# tie-flash-cfg.net
KiCad netlist of a schematic drawn in Altium Designer
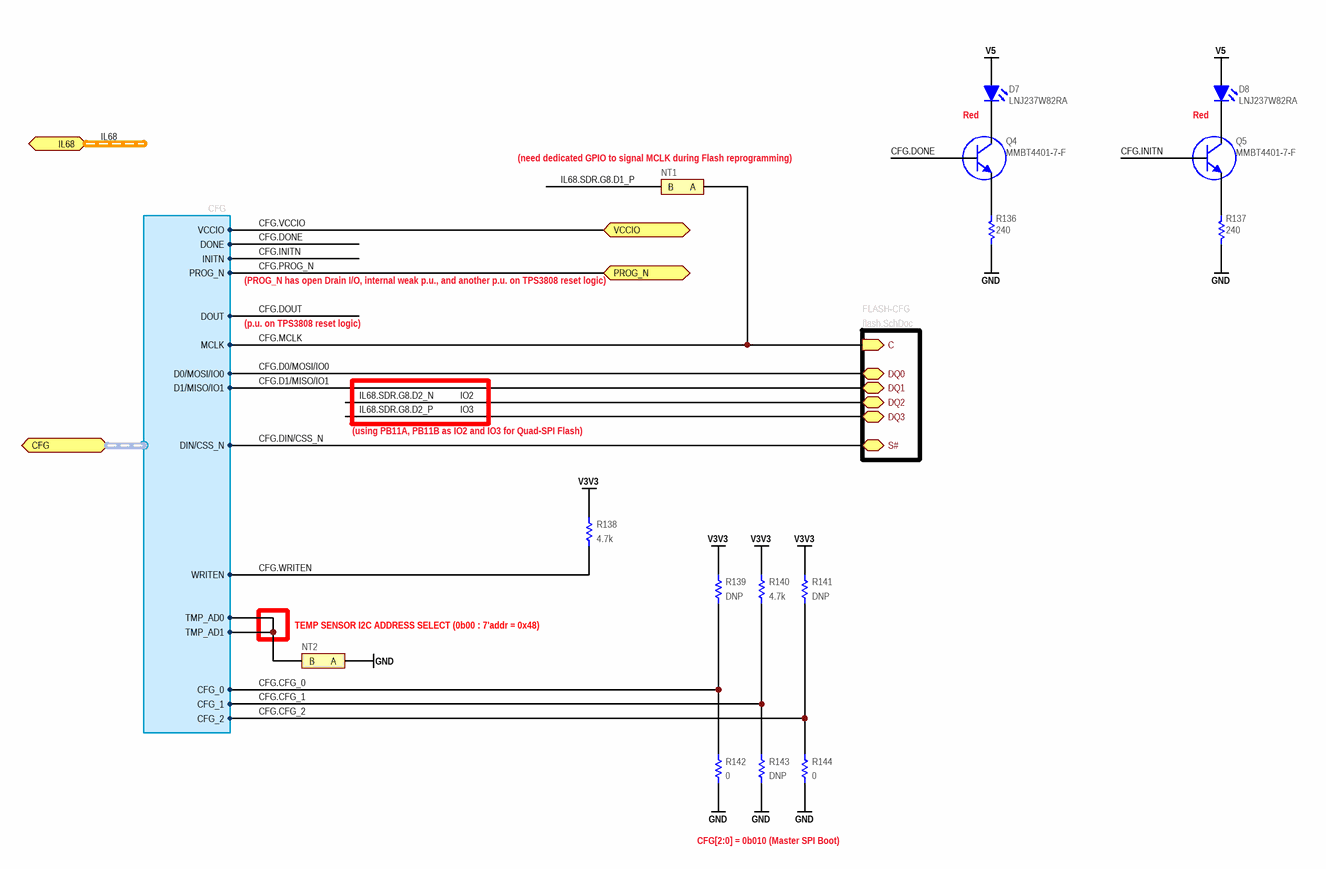
[diagram p0: tie-flash-cfg.SchDoc]

(export (version "E")
  (design (tool "Eeschema 10.0.6"))
  (components
    (comp (ref "D7")
      (value "LNJ237W82RA")
      (footprint "0603_LED")
      (description "LED, SMT 0603, Color Red, 5mA, 1.85V")
      (fields (field (name "MANUFACTURER") "Panasonic"))
      (libsource (lib "generic") (part "LED0603RD"))
    )
    (comp (ref "D8")
      (value "LNJ237W82RA")
      (footprint "0603_LED")
      (description "LED, SMT 0603, Color Red, 5mA, 1.85V")
      (fields (field (name "MANUFACTURER") "Panasonic"))
      (libsource (lib "generic") (part "LED0603RD"))
    )
    (comp (ref "NT1")
      (value "NET_TIE")
      (footprint "NET_TIE")
      (libsource (lib "copper_suicide") (part "NET_TIE"))
    )
    (comp (ref "NT2")
      (value "NET_TIE")
      (footprint "NET_TIE")
      (libsource (lib "copper_suicide") (part "NET_TIE"))
    )
    (comp (ref "Q4")
      (value "MMBT4401-7-F")
      (footprint "generic:SOT23")
      (description "NPN Small Signal Transistor SMD SOT-23")
      (fields (field (name "MANUFACTURER P/N") "MMBT4401-7-F") (field (name "MANUFACTURER") "Diodes, Inc."))
      (libsource (lib "diodes_inc") (part "MMBT4401-7-F"))
    )
    (comp (ref "Q5")
      (value "MMBT4401-7-F")
      (footprint "generic:SOT23")
      (description "NPN Small Signal Transistor SMD SOT-23")
      (fields (field (name "MANUFACTURER P/N") "MMBT4401-7-F") (field (name "MANUFACTURER") "Diodes, Inc."))
      (libsource (lib "diodes_inc") (part "MMBT4401-7-F"))
    )
    (comp (ref "R136")
      (value "240")
      (footprint "RESC1005X40N")
      (description "Thick Film Resistor 240 ±1% 0.1W 75V 0402")
      (fields (field (name "TOLERANCE") "±1%") (field (name "MANUFACTURER") "Panasonic"))
      (libsource (lib "generic") (part "RES"))
    )
    (comp (ref "R137")
      (value "240")
      (footprint "RESC1005X40N")
      (description "Thick Film Resistor 240 ±1% 0.1W 75V 0402")
      (fields (field (name "TOLERANCE") "±1%") (field (name "MANUFACTURER") "Panasonic"))
      (libsource (lib "generic") (part "RES"))
    )
    (comp (ref "R138")
      (value "4.7k")
      (footprint "RESC1005X40N")
      (description "Thick Film Resistor 4.7k ±1% 0.1W 75V 0402")
      (fields (field (name "TOLERANCE") "±1%") (field (name "MANUFACTURER") "Panasonic"))
      (libsource (lib "generic") (part "RES"))
    )
    (comp (ref "R139")
      (value "ERJ-3EKF4701V")
      (footprint "RESC1608X55N")
      (description "Thick Film Resistor 4.7k ±1% 0.1W 50V 0603")
      (fields
        (field (name "TOLERANCE") "±1%")
        (field (name "MANUFACTURER") "Panasonic")
        (field (name "DO NOT PLACE") "DNP")
      )
      (libsource (lib "generic") (part "RES"))
    )
    (comp (ref "R140")
      (value "4.7k")
      (footprint "RESC1608X55N")
      (description "Thick Film Resistor 4.7k ±1% 0.1W 50V 0603")
      (fields (field (name "TOLERANCE") "±1%") (field (name "MANUFACTURER") "Panasonic"))
      (libsource (lib "generic") (part "RES"))
    )
    (comp (ref "R141")
      (value "ERJ-3EKF4701V")
      (footprint "RESC1608X55N")
      (description "Thick Film Resistor 4.7k ±1% 0.1W 50V 0603")
      (fields
        (field (name "TOLERANCE") "±1%")
        (field (name "MANUFACTURER") "Panasonic")
        (field (name "DO NOT PLACE") "DNP")
      )
      (libsource (lib "generic") (part "RES"))
    )
    (comp (ref "R142")
      (value "0")
      (footprint "RESC1608X55N")
      (description "Thick Film Resistor Jumper 0 1A 0603")
      (fields (field (name "TOLERANCE") "±1%") (field (name "MANUFACTURER") "Panasonic"))
      (libsource (lib "generic") (part "RES"))
    )
    (comp (ref "R143")
      (value "ERJ-3GEY0R00V")
      (footprint "RESC1608X55N")
      (description "Thick Film Resistor Jumper 0 1A 0603")
      (fields
        (field (name "TOLERANCE") "±1%")
        (field (name "MANUFACTURER") "Panasonic")
        (field (name "DO NOT PLACE") "DNP")
      )
      (libsource (lib "generic") (part "RES"))
    )
    (comp (ref "R144")
      (value "0")
      (footprint "RESC1608X55N")
      (description "Thick Film Resistor Jumper 0 1A 0603")
      (fields (field (name "TOLERANCE") "±1%") (field (name "MANUFACTURER") "Panasonic"))
      (libsource (lib "generic") (part "RES"))
    )
  )
  (nets
    (net (code "3") (name "/CFG.CFG_0") (class "Default")
      (node (ref "R139") (pin "1") (pinfunction "1_1") (pintype "passive"))
      (node (ref "R142") (pin "2") (pinfunction "2_2") (pintype "passive"))
    )
    (net (code "4") (name "/CFG.CFG_1") (class "Default")
      (node (ref "R140") (pin "1") (pinfunction "1_1") (pintype "passive"))
      (node (ref "R143") (pin "2") (pinfunction "2_2") (pintype "passive"))
    )
    (net (code "5") (name "/CFG.CFG_2") (class "Default")
      (node (ref "R141") (pin "1") (pinfunction "1_1") (pintype "passive"))
      (node (ref "R144") (pin "2") (pinfunction "2_2") (pintype "passive"))
    )
    (net (code "9") (name "/CFG.DONE") (class "Default")
      (node (ref "Q4") (pin "1") (pinfunction "B_1") (pintype "passive"))
    )
    (net (code "11") (name "/CFG.INITN") (class "Default")
      (node (ref "Q5") (pin "1") (pinfunction "B_1") (pintype "passive"))
    )
    (net (code "12") (name "/CFG.MCLK") (class "Default")
      (node (ref "NT1") (pin "A") (pinfunction "A_A") (pintype "passive"))
    )
    (net (code "15") (name "/CFG.WRITEN") (class "Default")
      (node (ref "R138") (pin "1") (pinfunction "1_1") (pintype "passive"))
    )
    (net (code "16") (name "/IL68.SDR.G8.D1_P") (class "Default")
      (node (ref "NT1") (pin "B") (pinfunction "B_B") (pintype "passive"))
    )
    (net (code "19") (name "/TMP_AD0") (class "Default")
      (node (ref "NT2") (pin "B") (pinfunction "B_B") (pintype "passive"))
    )
    (net (code "22") (name "GND") (class "Default")
      (node (ref "NT2") (pin "A") (pinfunction "A_A") (pintype "passive"))
      (node (ref "R136") (pin "2") (pinfunction "2_2") (pintype "passive"))
      (node (ref "R137") (pin "2") (pinfunction "2_2") (pintype "passive"))
      (node (ref "R142") (pin "1") (pinfunction "1_1") (pintype "passive"))
      (node (ref "R143") (pin "1") (pinfunction "1_1") (pintype "passive"))
      (node (ref "R144") (pin "1") (pinfunction "1_1") (pintype "passive"))
    )
    (net (code "23") (name "Net-(D7-K)") (class "Default")
      (node (ref "D7") (pin "2") (pinfunction "K_2") (pintype "passive"))
      (node (ref "Q4") (pin "3") (pinfunction "C_3") (pintype "passive"))
    )
    (net (code "24") (name "Net-(D8-K)") (class "Default")
      (node (ref "D8") (pin "2") (pinfunction "K_2") (pintype "passive"))
      (node (ref "Q5") (pin "3") (pinfunction "C_3") (pintype "passive"))
    )
    (net (code "25") (name "Net-(Q4-E)") (class "Default")
      (node (ref "Q4") (pin "2") (pinfunction "E_2") (pintype "passive"))
      (node (ref "R136") (pin "1") (pinfunction "1_1") (pintype "passive"))
    )
    (net (code "26") (name "Net-(Q5-E)") (class "Default")
      (node (ref "Q5") (pin "2") (pinfunction "E_2") (pintype "passive"))
      (node (ref "R137") (pin "1") (pinfunction "1_1") (pintype "passive"))
    )
    (net (code "27") (name "V3V3") (class "Default")
      (node (ref "R138") (pin "2") (pinfunction "2_2") (pintype "passive"))
      (node (ref "R139") (pin "2") (pinfunction "2_2") (pintype "passive"))
      (node (ref "R140") (pin "2") (pinfunction "2_2") (pintype "passive"))
      (node (ref "R141") (pin "2") (pinfunction "2_2") (pintype "passive"))
    )
    (net (code "28") (name "V5") (class "Default")
      (node (ref "D7") (pin "1") (pinfunction "A_1") (pintype "passive"))
      (node (ref "D8") (pin "1") (pinfunction "A_1") (pintype "passive"))
    )
  )
)
